# ma700_breakout.net
KiCad netlist of a schematic drawn in EAGLE
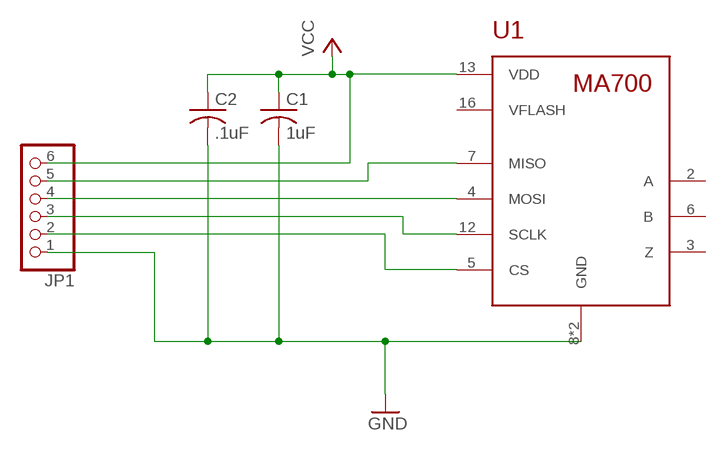
[diagram p0: schematic, sheet 1]

(export (version "E")
  (design (tool "Eeschema 10.0.6"))
  (components
    (comp (ref "C1")
      (value "1uF")
      (footprint "eagle-import:C0603")
      (libsource (lib "eagle-import") (part "C-USC0603"))
    )
    (comp (ref "C2")
      (value ".1uF")
      (footprint "eagle-import:C0603")
      (libsource (lib "eagle-import") (part "C-USC0603"))
    )
    (comp (ref "JP1")
      (value "PINHD-1X6")
      (footprint "eagle-import:1X06")
      (libsource (lib "eagle-import") (part "PINHD-1X6"))
    )
    (comp (ref "U1")
      (value "MA700")
      (footprint "eagle-import:QFN-16")
      (libsource (lib "eagle-import") (part "MA700"))
    )
  )
  (nets
    (net (code "1") (name "GND") (class "Default")
      (node (ref "C1") (pin "2") (pinfunction "2_2") (pintype "passive"))
      (node (ref "C2") (pin "2") (pinfunction "2_2") (pintype "passive"))
      (node (ref "JP1") (pin "1") (pinfunction "1_1") (pintype "passive"))
      (node (ref "U1") (pin "8") (pinfunction "GND_8") (pintype "bidirectional"))
      (node (ref "U1") (pin "PAD") (pinfunction "GND_PAD") (pintype "bidirectional"))
    )
    (net (code "2") (name "Net-(U1-CS)") (class "Default")
      (node (ref "JP1") (pin "2") (pinfunction "2_2") (pintype "passive"))
      (node (ref "U1") (pin "5") (pinfunction "CS_5") (pintype "bidirectional"))
    )
    (net (code "3") (name "Net-(U1-MISO)") (class "Default")
      (node (ref "JP1") (pin "5") (pinfunction "5_5") (pintype "passive"))
      (node (ref "U1") (pin "7") (pinfunction "MISO_7") (pintype "bidirectional"))
    )
    (net (code "4") (name "Net-(U1-MOSI)") (class "Default")
      (node (ref "JP1") (pin "4") (pinfunction "4_4") (pintype "passive"))
      (node (ref "U1") (pin "4") (pinfunction "MOSI_4") (pintype "bidirectional"))
    )
    (net (code "5") (name "Net-(U1-SCLK)") (class "Default")
      (node (ref "JP1") (pin "3") (pinfunction "3_3") (pintype "passive"))
      (node (ref "U1") (pin "12") (pinfunction "SCLK_12") (pintype "bidirectional"))
    )
    (net (code "6") (name "VCC") (class "Default")
      (node (ref "C1") (pin "1") (pinfunction "1_1") (pintype "passive"))
      (node (ref "C2") (pin "1") (pinfunction "1_1") (pintype "passive"))
      (node (ref "JP1") (pin "6") (pinfunction "6_6") (pintype "passive"))
      (node (ref "U1") (pin "13") (pinfunction "VDD_13") (pintype "bidirectional"))
    )
    (net (code "7") (name "unconnected-(U1-A-Pad2)") (class "Default")
      (node (ref "U1") (pin "2") (pinfunction "A_2") (pintype "bidirectional"))
    )
    (net (code "8") (name "unconnected-(U1-B-Pad6)") (class "Default")
      (node (ref "U1") (pin "6") (pinfunction "B_6") (pintype "bidirectional"))
    )
    (net (code "9") (name "unconnected-(U1-VFLASH-Pad16)") (class "Default")
      (node (ref "U1") (pin "16") (pinfunction "VFLASH_16") (pintype "bidirectional"))
    )
    (net (code "10") (name "unconnected-(U1-Z-Pad3)") (class "Default")
      (node (ref "U1") (pin "3") (pinfunction "Z_3") (pintype "bidirectional"))
    )
  )
)
